# MSX_Keyboard_USB.net
KiCad netlist of a schematic drawn in EasyEDA
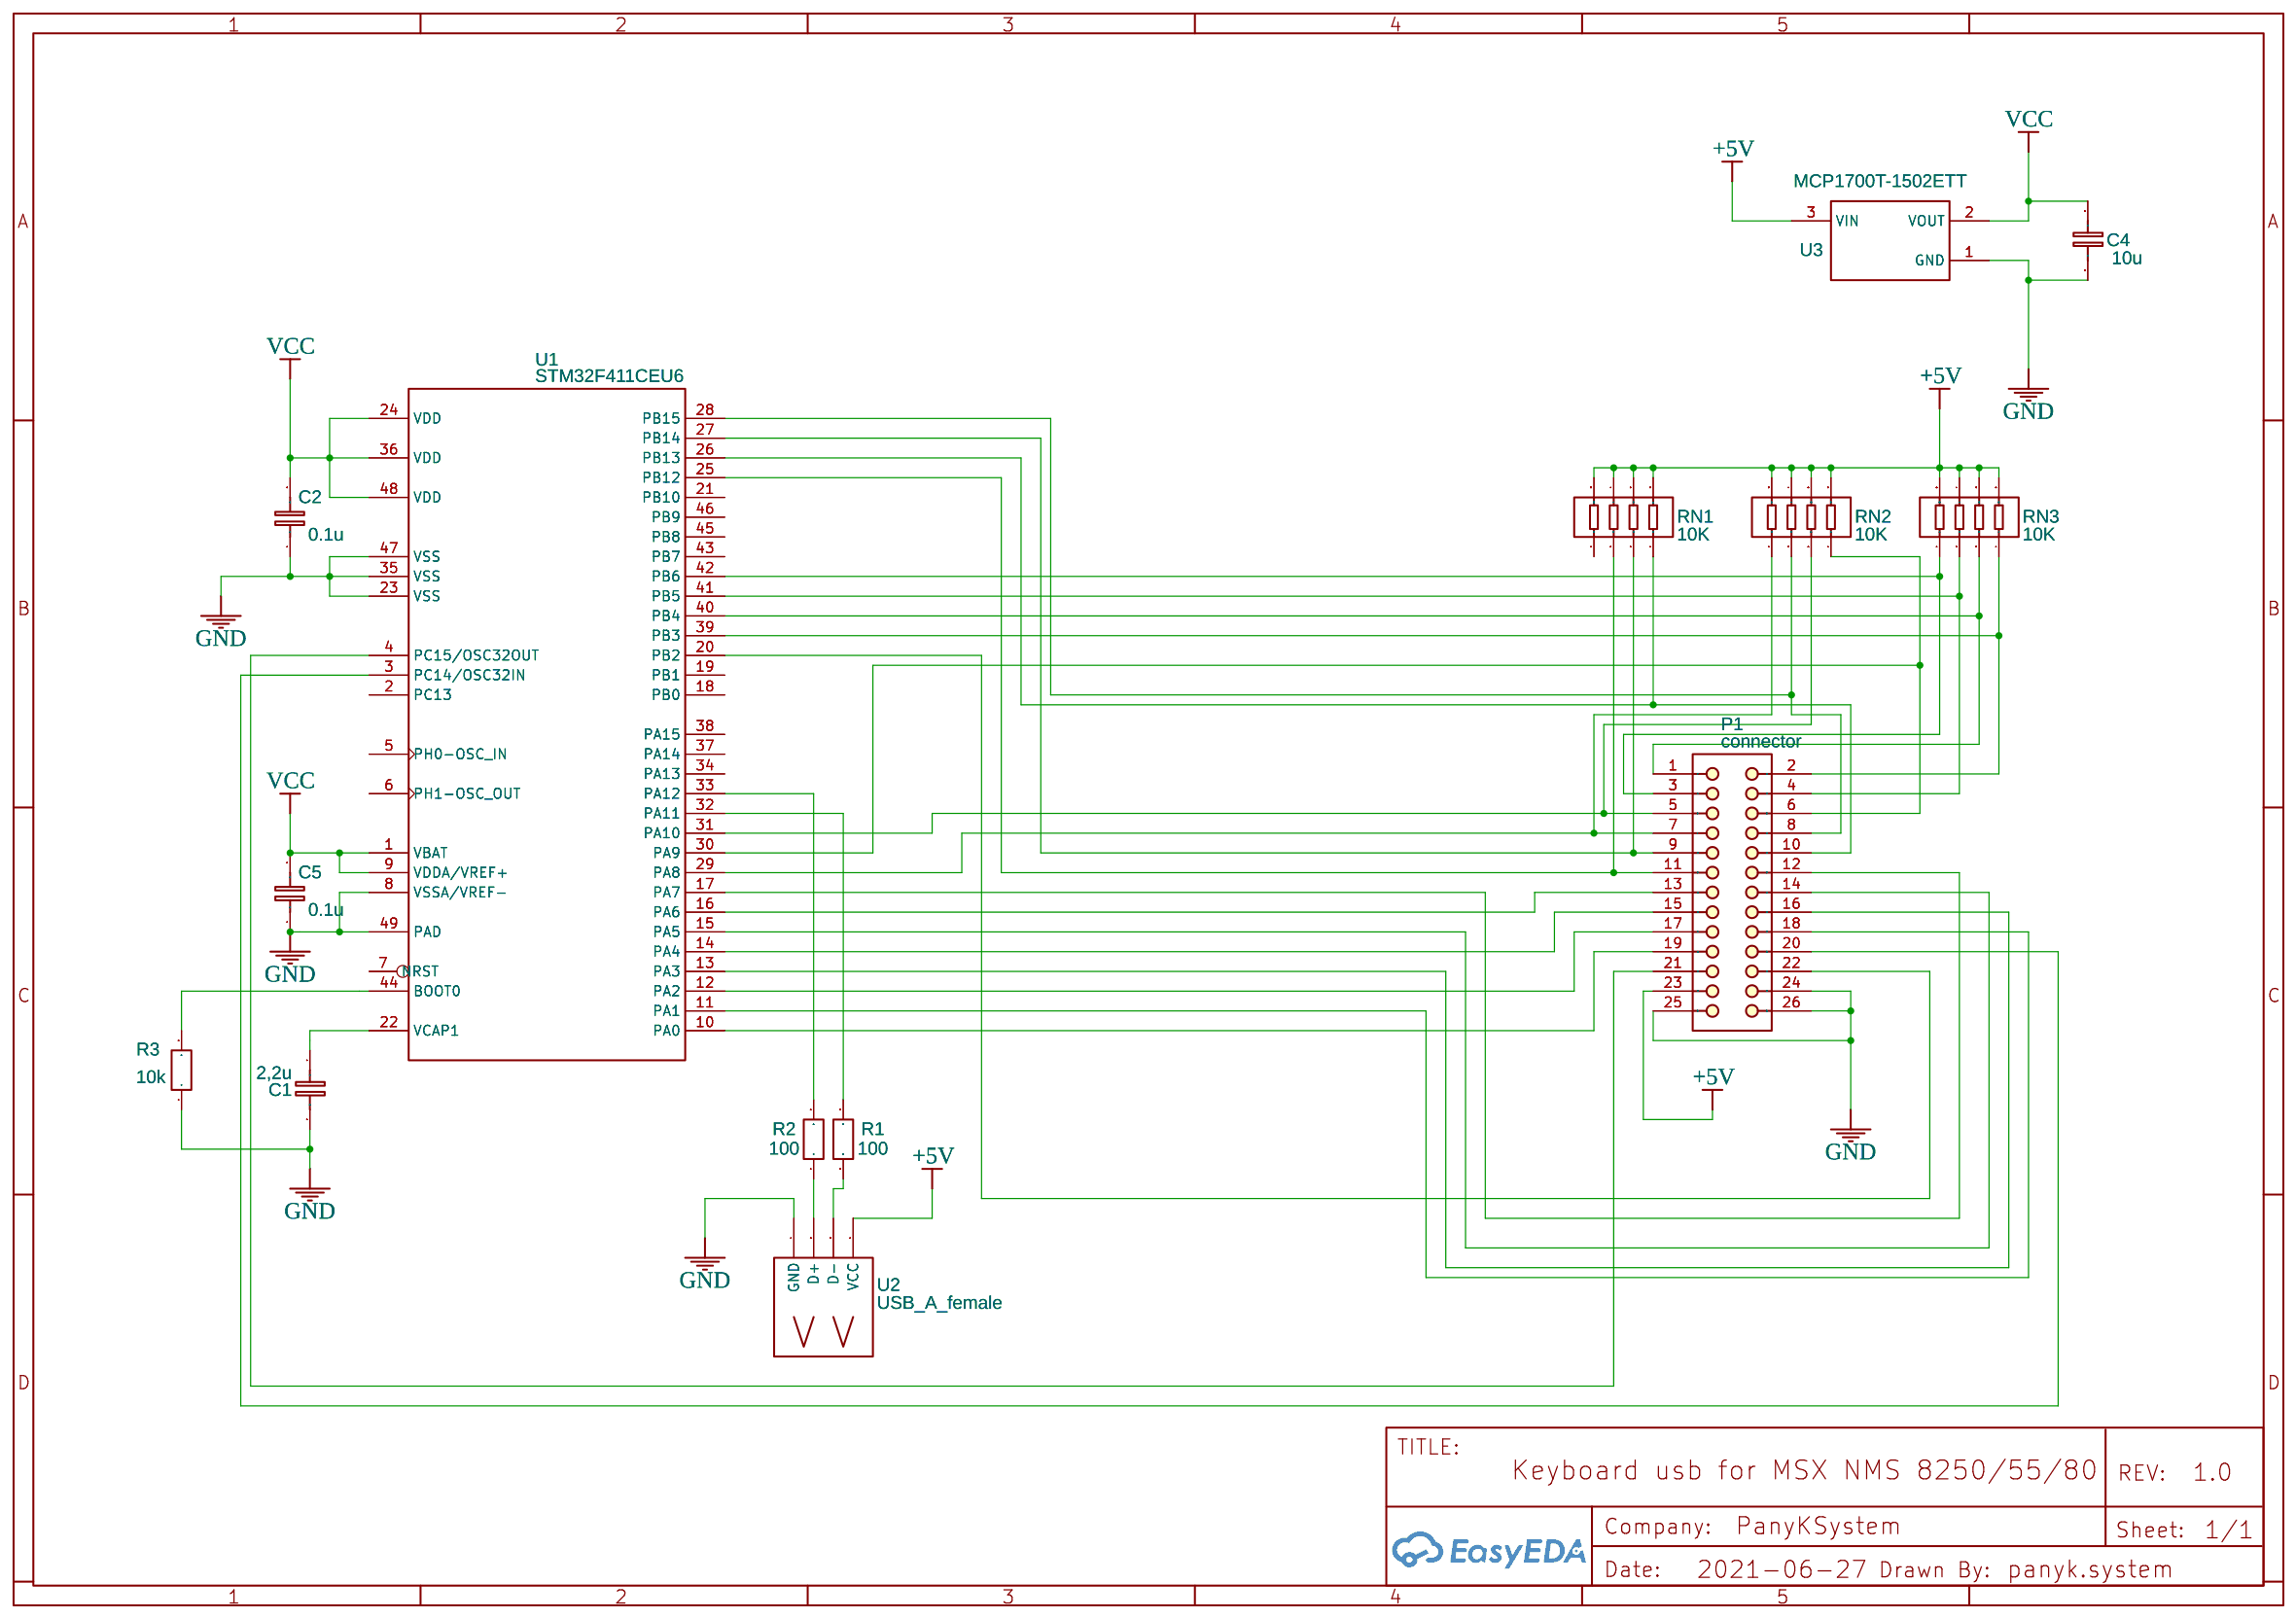
[diagram p0: schematic sheet]

(export (version "E")
  (design (tool "Eeschema 10.0.6"))
  (components
    (comp (ref "C1") (value "2,2u") (libsource (lib "") (part "C_0805_EU_1")))
    (comp (ref "C2") (value "0.1u") (libsource (lib "") (part "C_0805_EU_3")))
    (comp (ref "C4") (value "10u") (libsource (lib "") (part "C_0805_EU_2")))
    (comp (ref "C5") (value "0.1u") (libsource (lib "") (part "C_0805_EU")))
    (comp (ref "P1") (value "connector") (libsource (lib "") (part "connector")))
    (comp (ref "R1") (value "100") (libsource (lib "") (part "R_0603_EU")))
    (comp (ref "R2") (value "100") (libsource (lib "") (part "R_0603_EU")))
    (comp (ref "R3") (value "10k") (libsource (lib "") (part "R_0603_EU")))
    (comp (ref "RN1")
      (value "10K")
      (fields
        (field (name "BOM_Manufacturer Part") "4D03WGF1002T5E")
        (field (name "BOM_Supplier Part") "C425238")
      )
      (libsource (lib "") (part "4D03WGF1002T5E"))
    )
    (comp (ref "RN2")
      (value "10K")
      (fields
        (field (name "BOM_Manufacturer Part") "4D03WGF1002T5E")
        (field (name "BOM_Supplier Part") "C425238")
      )
      (libsource (lib "") (part "4D03WGF1002T5E"))
    )
    (comp (ref "RN3")
      (value "10K")
      (fields
        (field (name "BOM_Manufacturer Part") "4D03WGF1002T5E")
        (field (name "BOM_Supplier Part") "C425238")
      )
      (libsource (lib "") (part "4D03WGF1002T5E"))
    )
    (comp (ref "U1")
      (value "STM32F411CEU6")
      (fields (field (name "BOM_Supplier Part") "C60420"))
      (libsource (lib "") (part "STM32F411CEU6"))
    )
    (comp (ref "U2") (value "USB_A_female") (libsource (lib "") (part "USB_A_female")))
    (comp (ref "U3") (value "MCP1700T-1502ETT") (libsource (lib "") (part "MCP1700T-1502ETT")))
  )
  (nets
    (net (code "1") (name "+5V") (class "Default")
      (node (ref "P1") (pin "23") (pinfunction "23_23") (pintype "unspecified"))
      (node (ref "RN1") (pin "5") (pinfunction "5_5") (pintype "unspecified"))
      (node (ref "RN1") (pin "6") (pinfunction "6_6") (pintype "unspecified"))
      (node (ref "RN1") (pin "7") (pinfunction "7_7") (pintype "unspecified"))
      (node (ref "RN1") (pin "8") (pinfunction "8_8") (pintype "unspecified"))
      (node (ref "RN2") (pin "5") (pinfunction "5_5") (pintype "unspecified"))
      (node (ref "RN2") (pin "6") (pinfunction "6_6") (pintype "unspecified"))
      (node (ref "RN2") (pin "7") (pinfunction "7_7") (pintype "unspecified"))
      (node (ref "RN2") (pin "8") (pinfunction "8_8") (pintype "unspecified"))
      (node (ref "RN3") (pin "5") (pinfunction "5_5") (pintype "unspecified"))
      (node (ref "RN3") (pin "6") (pinfunction "6_6") (pintype "unspecified"))
      (node (ref "RN3") (pin "7") (pinfunction "7_7") (pintype "unspecified"))
      (node (ref "RN3") (pin "8") (pinfunction "8_8") (pintype "unspecified"))
      (node (ref "U2") (pin "1") (pinfunction "VCC_1") (pintype "unspecified"))
      (node (ref "U3") (pin "3") (pinfunction "VIN_3") (pintype "passive"))
    )
    (net (code "2") (name "GND") (class "Default")
      (node (ref "C1") (pin "2") (pinfunction "2_2") (pintype "unspecified"))
      (node (ref "C2") (pin "1") (pinfunction "1_1") (pintype "unspecified"))
      (node (ref "C4") (pin "2") (pinfunction "2_2") (pintype "unspecified"))
      (node (ref "C5") (pin "1") (pinfunction "1_1") (pintype "unspecified"))
      (node (ref "P1") (pin "24") (pinfunction "24_24") (pintype "unspecified"))
      (node (ref "P1") (pin "25") (pinfunction "25_25") (pintype "unspecified"))
      (node (ref "P1") (pin "26") (pinfunction "26_26") (pintype "unspecified"))
      (node (ref "R3") (pin "1") (pinfunction "1_1") (pintype "unspecified"))
      (node (ref "U1") (pin "23") (pinfunction "VSS_23") (pintype "unspecified"))
      (node (ref "U1") (pin "35") (pinfunction "VSS_35") (pintype "unspecified"))
      (node (ref "U1") (pin "47") (pinfunction "VSS_47") (pintype "unspecified"))
      (node (ref "U1") (pin "49") (pinfunction "PAD_49") (pintype "passive"))
      (node (ref "U1") (pin "8") (pinfunction "VSSA/VREF-_8") (pintype "passive"))
      (node (ref "U2") (pin "4") (pinfunction "GND_4") (pintype "unspecified"))
      (node (ref "U3") (pin "1") (pinfunction "GND_1") (pintype "passive"))
    )
    (net (code "3") (name "Net-(U1-BOOT0)") (class "Default")
      (node (ref "R3") (pin "2") (pinfunction "2_2") (pintype "unspecified"))
      (node (ref "U1") (pin "44") (pinfunction "BOOT0_44") (pintype "input"))
    )
    (net (code "4") (name "Net-(U1-PA0)") (class "Default")
      (node (ref "P1") (pin "19") (pinfunction "19_19") (pintype "unspecified"))
      (node (ref "U1") (pin "10") (pinfunction "PA0_10") (pintype "unspecified"))
    )
    (net (code "5") (name "Net-(U1-PA1)") (class "Default")
      (node (ref "P1") (pin "18") (pinfunction "18_18") (pintype "unspecified"))
      (node (ref "U1") (pin "11") (pinfunction "PA1_11") (pintype "unspecified"))
    )
    (net (code "6") (name "Net-(U1-PA2)") (class "Default")
      (node (ref "P1") (pin "17") (pinfunction "17_17") (pintype "unspecified"))
      (node (ref "U1") (pin "12") (pinfunction "PA2_12") (pintype "unspecified"))
    )
    (net (code "7") (name "Net-(U1-PA3)") (class "Default")
      (node (ref "P1") (pin "16") (pinfunction "16_16") (pintype "unspecified"))
      (node (ref "U1") (pin "13") (pinfunction "PA3_13") (pintype "unspecified"))
    )
    (net (code "8") (name "Net-(U1-PA4)") (class "Default")
      (node (ref "P1") (pin "15") (pinfunction "15_15") (pintype "unspecified"))
      (node (ref "U1") (pin "14") (pinfunction "PA4_14") (pintype "unspecified"))
    )
    (net (code "9") (name "Net-(U1-PA5)") (class "Default")
      (node (ref "P1") (pin "14") (pinfunction "14_14") (pintype "unspecified"))
      (node (ref "U1") (pin "15") (pinfunction "PA5_15") (pintype "unspecified"))
    )
    (net (code "10") (name "Net-(U1-PA6)") (class "Default")
      (node (ref "P1") (pin "13") (pinfunction "13_13") (pintype "unspecified"))
      (node (ref "U1") (pin "16") (pinfunction "PA6_16") (pintype "unspecified"))
    )
    (net (code "11") (name "Net-(U1-PA7)") (class "Default")
      (node (ref "P1") (pin "12") (pinfunction "12_12") (pintype "unspecified"))
      (node (ref "U1") (pin "17") (pinfunction "PA7_17") (pintype "unspecified"))
    )
    (net (code "12") (name "Net-(U1-PA8)") (class "Default")
      (node (ref "P1") (pin "7") (pinfunction "7_7") (pintype "unspecified"))
      (node (ref "RN2") (pin "1") (pinfunction "1_1") (pintype "unspecified"))
      (node (ref "U1") (pin "29") (pinfunction "PA8_29") (pintype "unspecified"))
    )
    (net (code "13") (name "Net-(U1-PA9)") (class "Default")
      (node (ref "P1") (pin "6") (pinfunction "6_6") (pintype "unspecified"))
      (node (ref "RN2") (pin "4") (pinfunction "4_4") (pintype "unspecified"))
      (node (ref "U1") (pin "30") (pinfunction "PA9_30") (pintype "unspecified"))
    )
    (net (code "14") (name "Net-(U1-PA10)") (class "Default")
      (node (ref "P1") (pin "5") (pinfunction "5_5") (pintype "unspecified"))
      (node (ref "RN2") (pin "3") (pinfunction "3_3") (pintype "unspecified"))
      (node (ref "U1") (pin "31") (pinfunction "PA10_31") (pintype "unspecified"))
    )
    (net (code "15") (name "Net-(U1-PA11)") (class "Default")
      (node (ref "R1") (pin "2") (pinfunction "2_2") (pintype "unspecified"))
      (node (ref "U1") (pin "32") (pinfunction "PA11_32") (pintype "unspecified"))
    )
    (net (code "16") (name "Net-(U1-PA12)") (class "Default")
      (node (ref "R2") (pin "2") (pinfunction "2_2") (pintype "unspecified"))
      (node (ref "U1") (pin "33") (pinfunction "PA12_33") (pintype "unspecified"))
    )
    (net (code "17") (name "Net-(U1-PB2)") (class "Default")
      (node (ref "P1") (pin "22") (pinfunction "22_22") (pintype "unspecified"))
      (node (ref "U1") (pin "20") (pinfunction "PB2_20") (pintype "unspecified"))
    )
    (net (code "18") (name "Net-(U1-PB3)") (class "Default")
      (node (ref "P1") (pin "2") (pinfunction "2_2") (pintype "unspecified"))
      (node (ref "RN3") (pin "4") (pinfunction "4_4") (pintype "unspecified"))
      (node (ref "U1") (pin "39") (pinfunction "PB3_39") (pintype "unspecified"))
    )
    (net (code "19") (name "Net-(U1-PB4)") (class "Default")
      (node (ref "P1") (pin "1") (pinfunction "1_1") (pintype "unspecified"))
      (node (ref "RN3") (pin "3") (pinfunction "3_3") (pintype "unspecified"))
      (node (ref "U1") (pin "40") (pinfunction "PB4_40") (pintype "unspecified"))
    )
    (net (code "20") (name "Net-(U1-PB5)") (class "Default")
      (node (ref "P1") (pin "4") (pinfunction "4_4") (pintype "unspecified"))
      (node (ref "RN3") (pin "2") (pinfunction "2_2") (pintype "unspecified"))
      (node (ref "U1") (pin "41") (pinfunction "PB5_41") (pintype "unspecified"))
    )
    (net (code "21") (name "Net-(U1-PB6)") (class "Default")
      (node (ref "P1") (pin "3") (pinfunction "3_3") (pintype "unspecified"))
      (node (ref "RN3") (pin "1") (pinfunction "1_1") (pintype "unspecified"))
      (node (ref "U1") (pin "42") (pinfunction "PB6_42") (pintype "unspecified"))
    )
    (net (code "22") (name "Net-(U1-PB12)") (class "Default")
      (node (ref "P1") (pin "11") (pinfunction "11_11") (pintype "unspecified"))
      (node (ref "RN1") (pin "2") (pinfunction "2_2") (pintype "unspecified"))
      (node (ref "U1") (pin "25") (pinfunction "PB12_25") (pintype "unspecified"))
    )
    (net (code "23") (name "Net-(U1-PB13)") (class "Default")
      (node (ref "P1") (pin "10") (pinfunction "10_10") (pintype "unspecified"))
      (node (ref "RN1") (pin "4") (pinfunction "4_4") (pintype "unspecified"))
      (node (ref "U1") (pin "26") (pinfunction "PB13_26") (pintype "unspecified"))
    )
    (net (code "24") (name "Net-(U1-PB14)") (class "Default")
      (node (ref "P1") (pin "9") (pinfunction "9_9") (pintype "unspecified"))
      (node (ref "RN1") (pin "3") (pinfunction "3_3") (pintype "unspecified"))
      (node (ref "U1") (pin "27") (pinfunction "PB14_27") (pintype "unspecified"))
    )
    (net (code "25") (name "Net-(U1-PB15)") (class "Default")
      (node (ref "P1") (pin "8") (pinfunction "8_8") (pintype "unspecified"))
      (node (ref "RN2") (pin "2") (pinfunction "2_2") (pintype "unspecified"))
      (node (ref "U1") (pin "28") (pinfunction "PB15_28") (pintype "unspecified"))
    )
    (net (code "26") (name "Net-(U1-PC14{slash}OSC32IN)") (class "Default")
      (node (ref "P1") (pin "20") (pinfunction "20_20") (pintype "unspecified"))
      (node (ref "U1") (pin "3") (pinfunction "PC14/OSC32IN_3") (pintype "unspecified"))
    )
    (net (code "27") (name "Net-(U1-PC15{slash}OSC32OUT)") (class "Default")
      (node (ref "P1") (pin "21") (pinfunction "21_21") (pintype "unspecified"))
      (node (ref "U1") (pin "4") (pinfunction "PC15/OSC32OUT_4") (pintype "unspecified"))
    )
    (net (code "28") (name "Net-(U1-VCAP1)") (class "Default")
      (node (ref "C1") (pin "1") (pinfunction "1_1") (pintype "unspecified"))
      (node (ref "U1") (pin "22") (pinfunction "VCAP1_22") (pintype "passive"))
    )
    (net (code "29") (name "Net-(U2-D+)") (class "Default")
      (node (ref "R2") (pin "1") (pinfunction "1_1") (pintype "unspecified"))
      (node (ref "U2") (pin "3") (pinfunction "D+_3") (pintype "unspecified"))
    )
    (net (code "30") (name "Net-(U2-D-)") (class "Default")
      (node (ref "R1") (pin "1") (pinfunction "1_1") (pintype "unspecified"))
      (node (ref "U2") (pin "2") (pinfunction "D-_2") (pintype "unspecified"))
    )
    (net (code "31") (name "VCC") (class "Default")
      (node (ref "C2") (pin "2") (pinfunction "2_2") (pintype "unspecified"))
      (node (ref "C4") (pin "1") (pinfunction "1_1") (pintype "unspecified"))
      (node (ref "C5") (pin "2") (pinfunction "2_2") (pintype "unspecified"))
      (node (ref "U1") (pin "1") (pinfunction "VBAT_1") (pintype "passive"))
      (node (ref "U1") (pin "24") (pinfunction "VDD_24") (pintype "unspecified"))
      (node (ref "U1") (pin "36") (pinfunction "VDD_36") (pintype "unspecified"))
      (node (ref "U1") (pin "48") (pinfunction "VDD_48") (pintype "unspecified"))
      (node (ref "U1") (pin "9") (pinfunction "VDDA/VREF+_9") (pintype "passive"))
      (node (ref "U3") (pin "2") (pinfunction "VOUT_2") (pintype "passive"))
    )
    (net (code "32") (name "unconnected-(RN1-Pad1)") (class "Default")
      (node (ref "RN1") (pin "1") (pinfunction "1_1") (pintype "unspecified"))
    )
    (net (code "33") (name "unconnected-(U1-NRST-Pad7)") (class "Default")
      (node (ref "U1") (pin "7") (pinfunction "NRST_7") (pintype "unspecified"))
    )
    (net (code "34") (name "unconnected-(U1-PA13-Pad34)") (class "Default")
      (node (ref "U1") (pin "34") (pinfunction "PA13_34") (pintype "unspecified"))
    )
    (net (code "35") (name "unconnected-(U1-PA14-Pad37)") (class "Default")
      (node (ref "U1") (pin "37") (pinfunction "PA14_37") (pintype "unspecified"))
    )
    (net (code "36") (name "unconnected-(U1-PA15-Pad38)") (class "Default")
      (node (ref "U1") (pin "38") (pinfunction "PA15_38") (pintype "unspecified"))
    )
    (net (code "37") (name "unconnected-(U1-PB0-Pad18)") (class "Default")
      (node (ref "U1") (pin "18") (pinfunction "PB0_18") (pintype "unspecified"))
    )
    (net (code "38") (name "unconnected-(U1-PB1-Pad19)") (class "Default")
      (node (ref "U1") (pin "19") (pinfunction "PB1_19") (pintype "unspecified"))
    )
    (net (code "39") (name "unconnected-(U1-PB7-Pad43)") (class "Default")
      (node (ref "U1") (pin "43") (pinfunction "PB7_43") (pintype "unspecified"))
    )
    (net (code "40") (name "unconnected-(U1-PB8-Pad45)") (class "Default")
      (node (ref "U1") (pin "45") (pinfunction "PB8_45") (pintype "unspecified"))
    )
    (net (code "41") (name "unconnected-(U1-PB9-Pad46)") (class "Default")
      (node (ref "U1") (pin "46") (pinfunction "PB9_46") (pintype "unspecified"))
    )
    (net (code "42") (name "unconnected-(U1-PB10-Pad21)") (class "Default")
      (node (ref "U1") (pin "21") (pinfunction "PB10_21") (pintype "unspecified"))
    )
    (net (code "43") (name "unconnected-(U1-PC13-Pad2)") (class "Default")
      (node (ref "U1") (pin "2") (pinfunction "PC13_2") (pintype "unspecified"))
    )
    (net (code "44") (name "unconnected-(U1-PH0-OSC_IN-Pad5)") (class "Default")
      (node (ref "U1") (pin "5") (pinfunction "PH0-OSC_IN_5") (pintype "unspecified"))
    )
    (net (code "45") (name "unconnected-(U1-PH1-OSC_OUT-Pad6)") (class "Default")
      (node (ref "U1") (pin "6") (pinfunction "PH1-OSC_OUT_6") (pintype "unspecified"))
    )
  )
)
